# GSM_GPS.net
KiCad netlist of a schematic drawn in Altium Designer
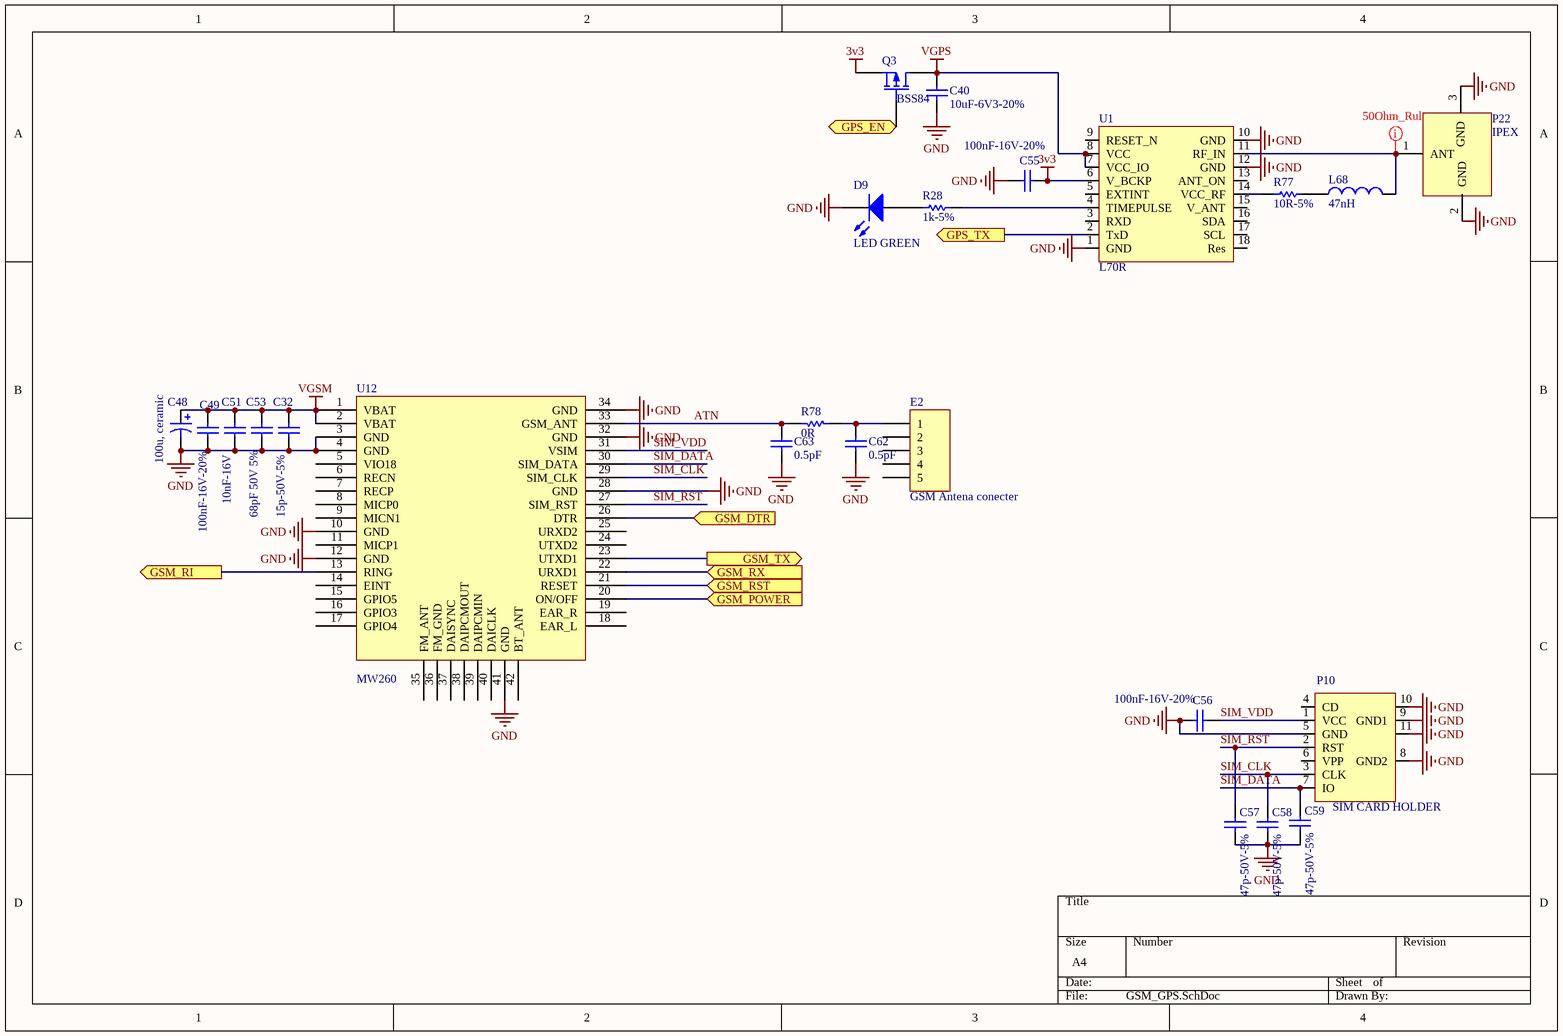
[diagram p0: GSM_GPS.SchDoc]

(export (version "E")
  (design (tool "Eeschema 10.0.6"))
  (components
    (comp (ref "C32")
      (value "15p-50V-5%")
      (footprint "C0402")
      (description "CAP CER 15PF 50V 5% NPO 0402")
      (fields
        (field (name "MANUFACTURER") "Yageo")
        (field (name "DIGI-KEY PART NUMBER") "311-1017-1-ND")
        (field (name "PUBLISHER") "Altium Limited")
      )
      (libsource (lib "Miscellaneous Devices") (part "Cap"))
    )
    (comp (ref "C40")
      (value "10uF-6V3-20%")
      (footprint "C0603")
      (description "CAP CER 10UF 6.3V 20% X5R 0603")
      (fields
        (field (name "MANUFACTURER") "Murata Electronics North America")
        (field (name "DIGI-KEY PART NUMBER") "490-3896-1-ND")
        (field (name "PUBLISHER") "Altium Limited")
      )
      (libsource (lib "Miscellaneous Devices") (part "Cap"))
    )
    (comp (ref "C48")
      (value "100u, ceramic")
      (footprint "C1812")
      (description "CAP CER 100UF 10V 20% X5R 1812")
      (fields
        (field (name "DIGI-KEY PART NUMBER") "445-7743-2-ND")
        (field (name "MANUFACTURER PART NUMBER") "C4532X5R1A107M")
        (field (name "PUBLISHER") "Altium Limited")
      )
      (libsource (lib "Miscellaneous Devices") (part "Cap Pol3"))
    )
    (comp (ref "C49")
      (value "100nF-16V-20%")
      (footprint "C0402")
      (description "CAP CER 0.1UF 16V Y5V 0402")
      (fields
        (field (name "MANUFACTURER") "Yageo")
        (field (name "DIGI-KEY PART NUMBER") "311-1047-1-ND")
        (field (name "PUBLISHER") "Altium Limited")
      )
      (libsource (lib "Miscellaneous Devices") (part "Cap"))
    )
    (comp (ref "C51")
      (value "10nF-16V")
      (footprint "C0402")
      (description "CAP CER 10000PF 16V 10% X7R 0402")
      (fields (field (name "DIGI-KEY PART NUMBER") "311-1042-2-ND") (field (name "MANUFACTURER") "Yageo"))
      (libsource (lib "Capacitor_0402") (part "10nF-16V-C0402-10%"))
    )
    (comp (ref "C53")
      (value "68pF 50V 5%")
      (footprint "C0402")
      (description "CAP CER 68PF 50V 5% NPO 0402")
      (fields (field (name "MANUFACTURER") "Yageo") (field (name "DIGI-KEY PART NUMBER") "311-1340-2-ND"))
      (libsource (lib "Miscellaneous Devices") (part "Cap"))
    )
    (comp (ref "C55")
      (value "100nF-16V-20%")
      (footprint "C0402")
      (description "CAP CER 0.1UF 16V Y5V 0402")
      (fields
        (field (name "MANUFACTURER") "Yageo")
        (field (name "DIGI-KEY PART NUMBER") "311-1047-1-ND")
        (field (name "PUBLISHER") "Altium Limited")
      )
      (libsource (lib "Miscellaneous Devices") (part "Cap"))
    )
    (comp (ref "C56")
      (value "100nF-16V-20%")
      (footprint "C0402")
      (description "CAP CER 0.1UF 16V Y5V 0402")
      (fields
        (field (name "MANUFACTURER") "Yageo")
        (field (name "DIGI-KEY PART NUMBER") "311-1047-1-ND")
        (field (name "PUBLISHER") "Altium Limited")
      )
      (libsource (lib "Miscellaneous Devices") (part "Cap"))
    )
    (comp (ref "C57")
      (value "47p-50V-5%")
      (footprint "C0402")
      (description "CAP CER 47PF 50V 5% NPO 0402")
      (fields
        (field (name "MANUFACTURER") "Yageo")
        (field (name "DIGI-KEY PART NUMBER") "311-1021-1-ND")
        (field (name "PUBLISHER") "Altium Limited")
      )
      (libsource (lib "Miscellaneous Devices") (part "Cap"))
    )
    (comp (ref "C58")
      (value "47p-50V-5%")
      (footprint "C0402")
      (description "CAP CER 47PF 50V 5% NPO 0402")
      (fields
        (field (name "MANUFACTURER") "Yageo")
        (field (name "DIGI-KEY PART NUMBER") "311-1021-1-ND")
        (field (name "PUBLISHER") "Altium Limited")
      )
      (libsource (lib "Miscellaneous Devices") (part "Cap"))
    )
    (comp (ref "C59")
      (value "47p-50V-5%")
      (footprint "C0402")
      (description "CAP CER 47PF 50V 5% NPO 0402")
      (fields
        (field (name "MANUFACTURER") "Yageo")
        (field (name "DIGI-KEY PART NUMBER") "311-1021-1-ND")
        (field (name "PUBLISHER") "Altium Limited")
      )
      (libsource (lib "Miscellaneous Devices") (part "Cap"))
    )
    (comp (ref "C62")
      (value "0.5pF")
      (footprint "C0402")
      (description "Non-Polarized Capacitor")
      (fields (field (name "DIGI-KEY PART NUMBER") "311-1094-1-ND") (field (name "MANUFACTURER") "Yageo"))
      (libsource (lib "Capacitor") (part "0.5pF-50V-C0805"))
    )
    (comp (ref "C63")
      (value "0.5pF")
      (footprint "C0402")
      (description "Non-Polarized Capacitor")
      (fields (field (name "DIGI-KEY PART NUMBER") "311-1094-1-ND") (field (name "MANUFACTURER") "Yageo"))
      (libsource (lib "Capacitor") (part "0.5pF-50V-C0805"))
    )
    (comp (ref "D9")
      (value "LED GREEN")
      (footprint "LED0603-G")
      (description "LED GREEN CLEAR THIN 0603 SMD")
      (fields
        (field (name "DIGI-KEY PART NUMBER") "160-1446-2-ND")
        (field (name "MANUFACTURER") "Lite-On Inc")
        (field (name "PUBLISHER") "Altium Limited")
      )
      (libsource (lib "Miscellaneous Devices") (part "LED2"))
    )
    (comp (ref "E2")
      (value "GSM Antena conecter")
      (footprint "A10343-GSM850/900/1800/1900/WCDMA")
      (description "Header, 5-Pin")
      (fields (field (name "PUBLISHER") "Altium Limited"))
      (libsource (lib "Miscellaneous Connectors") (part "Header 5"))
    )
    (comp (ref "L68")
      (value "47nH")
      (footprint "C0603")
      (description "Inductor")
      (fields (field (name "PUBLISHER") "Altium Limited"))
      (libsource (lib "Miscellaneous Devices") (part "Inductor"))
    )
    (comp (ref "P10")
      (value "SIM CARD HOLDER")
      (footprint "SIM MF01-412-063X")
      (description "SIM _CONNECTOR_410108105011-2LF")
      (fields (field (name "MANUFACTURER") "Tyrone"))
      (libsource (lib "Schlib1") (part "SIM CARD"))
    )
    (comp (ref "P22") (value "IPEX") (footprint "IPEX") (libsource (lib "Schlib1") (part "IPEX")))
    (comp (ref "Q3")
      (value "BSS84")
      (footprint "SOT23-3")
      (description "MOSFET P-CH 50V 130MA SOT23-3")
      (fields
        (field (name "DIGI-KEY PART NUMBER") "BSS84-FDITR-ND")
        (field (name "MANUFACTURER") "Diodes Inc")
        (field (name "PUBLISHER") "Altium Limited")
      )
      (libsource (lib "Miscellaneous Devices") (part "MOSFET-P"))
    )
    (comp (ref "R28")
      (value "1k-5%")
      (footprint "R0402")
      (description "RES 1.0K OHM 1/16W 5% 0402 SMD")
      (fields
        (field (name "DIGI-KEY PART NUMBER") "311-1.0KJRCT-ND")
        (field (name "MANUFACTURER") "Yageo")
        (field (name "PUBLISHER") "Altium Limited")
      )
      (libsource (lib "Miscellaneous Devices") (part "Res1"))
    )
    (comp (ref "R77")
      (value "10R-5%")
      (footprint "R0402")
      (description "RES 10 OHM 1/16W 5% 0402 SMD")
      (fields (field (name "DIGI-KEY PART NUMBER") "311-10JRTR-ND") (field (name "MANUFACTURER") "Yageo"))
      (libsource (lib "Resistor_0402") (part "10R-5%-R0402"))
    )
    (comp (ref "R78") (value "0R") (footprint "R0402") (libsource (lib "All_Resistor") (part "0R-0805")))
    (comp (ref "U1") (value "L70R") (footprint "MAX7") (libsource (lib "U-Blox") (part "MAX-7")))
    (comp (ref "U12")
      (value "MW260")
      (footprint "MW260-MODIFY")
      (description "THINK WILL GSM MODULE")
      (libsource (lib "Others") (part "GSM_MW260"))
    )
  )
  (nets
    (net (code "1") (name "/ATN") (class "Default")
      (node (ref "C63") (pin "2") (pinfunction "2_2") (pintype "passive"))
      (node (ref "R78") (pin "1") (pinfunction "1_1") (pintype "passive"))
      (node (ref "U12") (pin "33") (pinfunction "GSM_ANT_33") (pintype "passive"))
    )
    (net (code "2") (name "/GPS_EN") (class "Default")
      (node (ref "Q3") (pin "1") (pinfunction "G_1") (pintype "passive"))
    )
    (net (code "3") (name "/GPS_TX") (class "Default")
      (node (ref "U1") (pin "2") (pinfunction "TxD_2") (pintype "passive"))
    )
    (net (code "4") (name "/GSM_DTR") (class "Default")
      (node (ref "U12") (pin "26") (pinfunction "DTR_26") (pintype "passive"))
    )
    (net (code "5") (name "/GSM_POWER") (class "Default")
      (node (ref "U12") (pin "20") (pinfunction "ON/OFF_20") (pintype "passive"))
    )
    (net (code "6") (name "/GSM_RI") (class "Default")
      (node (ref "U12") (pin "13") (pinfunction "RING_13") (pintype "passive"))
    )
    (net (code "7") (name "/GSM_RST") (class "Default")
      (node (ref "U12") (pin "21") (pinfunction "RESET_21") (pintype "passive"))
    )
    (net (code "8") (name "/GSM_RX") (class "Default")
      (node (ref "U12") (pin "22") (pinfunction "URXD1_22") (pintype "passive"))
    )
    (net (code "9") (name "/GSM_TX") (class "Default")
      (node (ref "U12") (pin "23") (pinfunction "UTXD1_23") (pintype "passive"))
    )
    (net (code "10") (name "/SIM_CLK") (class "Default")
      (node (ref "C58") (pin "2") (pinfunction "2_2") (pintype "passive"))
      (node (ref "P10") (pin "3") (pinfunction "CLK_3") (pintype "passive"))
      (node (ref "U12") (pin "29") (pinfunction "SIM_CLK_29") (pintype "passive"))
    )
    (net (code "11") (name "/SIM_DATA") (class "Default")
      (node (ref "C59") (pin "2") (pinfunction "2_2") (pintype "passive"))
      (node (ref "P10") (pin "7") (pinfunction "IO_7") (pintype "passive"))
      (node (ref "U12") (pin "30") (pinfunction "SIM_DATA_30") (pintype "passive"))
    )
    (net (code "12") (name "/SIM_RST") (class "Default")
      (node (ref "C57") (pin "2") (pinfunction "2_2") (pintype "passive"))
      (node (ref "P10") (pin "2") (pinfunction "RST_2") (pintype "passive"))
      (node (ref "U12") (pin "27") (pinfunction "SIM_RST_27") (pintype "passive"))
    )
    (net (code "13") (name "/SIM_VDD") (class "Default")
      (node (ref "C56") (pin "1") (pinfunction "1_1") (pintype "passive"))
      (node (ref "P10") (pin "1") (pinfunction "VCC_1") (pintype "passive"))
      (node (ref "U12") (pin "31") (pinfunction "VSIM_31") (pintype "passive"))
    )
    (net (code "14") (name "3v3") (class "Default")
      (node (ref "C55") (pin "1") (pinfunction "1_1") (pintype "passive"))
      (node (ref "Q3") (pin "2") (pinfunction "S_2") (pintype "passive"))
      (node (ref "U1") (pin "6") (pinfunction "V_BCKP_6") (pintype "passive"))
    )
    (net (code "15") (name "GND") (class "Default")
      (node (ref "C32") (pin "2") (pinfunction "2_2") (pintype "passive"))
      (node (ref "C40") (pin "1") (pinfunction "1_1") (pintype "passive"))
      (node (ref "C48") (pin "2") (pinfunction "2_2") (pintype "passive"))
      (node (ref "C49") (pin "2") (pinfunction "2_2") (pintype "passive"))
      (node (ref "C51") (pin "1") (pinfunction "1_1") (pintype "passive"))
      (node (ref "C53") (pin "2") (pinfunction "2_2") (pintype "passive"))
      (node (ref "C55") (pin "2") (pinfunction "2_2") (pintype "passive"))
      (node (ref "C56") (pin "2") (pinfunction "2_2") (pintype "passive"))
      (node (ref "C57") (pin "1") (pinfunction "1_1") (pintype "passive"))
      (node (ref "C58") (pin "1") (pinfunction "1_1") (pintype "passive"))
      (node (ref "C59") (pin "1") (pinfunction "1_1") (pintype "passive"))
      (node (ref "C62") (pin "1") (pinfunction "1_1") (pintype "passive"))
      (node (ref "C63") (pin "1") (pinfunction "1_1") (pintype "passive"))
      (node (ref "D9") (pin "2") (pinfunction "K_2") (pintype "passive"))
      (node (ref "P10") (pin "10") (pinfunction "GND3_10") (pintype "passive"))
      (node (ref "P10") (pin "11") (pinfunction "GND4_11") (pintype "passive"))
      (node (ref "P10") (pin "5") (pinfunction "GND_5") (pintype "passive"))
      (node (ref "P10") (pin "8") (pinfunction "GND2_8") (pintype "passive"))
      (node (ref "P10") (pin "9") (pinfunction "GND1_9") (pintype "passive"))
      (node (ref "P22") (pin "2") (pinfunction "GND_2") (pintype "passive"))
      (node (ref "P22") (pin "3") (pinfunction "GND_3") (pintype "passive"))
      (node (ref "U1") (pin "1") (pinfunction "GND_1") (pintype "passive"))
      (node (ref "U1") (pin "10") (pinfunction "GND_10") (pintype "passive"))
      (node (ref "U1") (pin "12") (pinfunction "GND_12") (pintype "passive"))
      (node (ref "U12") (pin "10") (pinfunction "GND_10") (pintype "passive"))
      (node (ref "U12") (pin "12") (pinfunction "GND_12") (pintype "passive"))
      (node (ref "U12") (pin "28") (pinfunction "GND_28") (pintype "passive"))
      (node (ref "U12") (pin "3") (pinfunction "GND_3") (pintype "passive"))
      (node (ref "U12") (pin "32") (pinfunction "GND_32") (pintype "passive"))
      (node (ref "U12") (pin "34") (pinfunction "GND_34") (pintype "passive"))
      (node (ref "U12") (pin "4") (pinfunction "GND_4") (pintype "passive"))
      (node (ref "U12") (pin "41") (pinfunction "GND_41") (pintype "passive"))
    )
    (net (code "16") (name "Net-(C62-Pad2)") (class "Default")
      (node (ref "C62") (pin "2") (pinfunction "2_2") (pintype "passive"))
      (node (ref "E2") (pin "1") (pinfunction "1_1") (pintype "passive"))
      (node (ref "R78") (pin "2") (pinfunction "2_2") (pintype "passive"))
    )
    (net (code "17") (name "Net-(D9-A)") (class "Default")
      (node (ref "D9") (pin "1") (pinfunction "A_1") (pintype "passive"))
      (node (ref "R28") (pin "2") (pinfunction "2_2") (pintype "passive"))
    )
    (net (code "18") (name "Net-(L68-Pad1)") (class "Default")
      (node (ref "L68") (pin "1") (pinfunction "1_1") (pintype "passive"))
      (node (ref "R77") (pin "1") (pinfunction "1_1") (pintype "passive"))
    )
    (net (code "19") (name "Net-(P22-ANT)") (class "Default")
      (node (ref "L68") (pin "2") (pinfunction "2_2") (pintype "passive"))
      (node (ref "P22") (pin "1") (pinfunction "ANT_1") (pintype "passive"))
      (node (ref "U1") (pin "11") (pinfunction "RF_IN_11") (pintype "passive"))
    )
    (net (code "20") (name "Net-(U1-TIMEPULSE)") (class "Default")
      (node (ref "R28") (pin "1") (pinfunction "1_1") (pintype "passive"))
      (node (ref "U1") (pin "4") (pinfunction "TIMEPULSE_4") (pintype "passive"))
    )
    (net (code "21") (name "Net-(U1-VCC_RF)") (class "Default")
      (node (ref "R77") (pin "2") (pinfunction "2_2") (pintype "passive"))
      (node (ref "U1") (pin "14") (pinfunction "VCC_RF_14") (pintype "passive"))
    )
    (net (code "22") (name "VGPS") (class "Default")
      (node (ref "C40") (pin "2") (pinfunction "2_2") (pintype "passive"))
      (node (ref "Q3") (pin "3") (pinfunction "D_3") (pintype "passive"))
      (node (ref "U1") (pin "7") (pinfunction "VCC_IO_7") (pintype "passive"))
      (node (ref "U1") (pin "8") (pinfunction "VCC_8") (pintype "passive"))
    )
    (net (code "23") (name "VGSM") (class "Default")
      (node (ref "C32") (pin "1") (pinfunction "1_1") (pintype "passive"))
      (node (ref "C48") (pin "1") (pinfunction "1_1") (pintype "passive"))
      (node (ref "C49") (pin "1") (pinfunction "1_1") (pintype "passive"))
      (node (ref "C51") (pin "2") (pinfunction "2_2") (pintype "passive"))
      (node (ref "C53") (pin "1") (pinfunction "1_1") (pintype "passive"))
      (node (ref "U12") (pin "1") (pinfunction "VBAT_1") (pintype "passive"))
      (node (ref "U12") (pin "2") (pinfunction "VBAT_2") (pintype "passive"))
    )
    (net (code "24") (name "unconnected-(E2-Pad2)") (class "Default")
      (node (ref "E2") (pin "2") (pinfunction "2_2") (pintype "passive"))
    )
    (net (code "25") (name "unconnected-(E2-Pad3)") (class "Default")
      (node (ref "E2") (pin "3") (pinfunction "3_3") (pintype "passive"))
    )
    (net (code "26") (name "unconnected-(E2-Pad4)") (class "Default")
      (node (ref "E2") (pin "4") (pinfunction "4_4") (pintype "passive"))
    )
    (net (code "27") (name "unconnected-(E2-Pad5)") (class "Default")
      (node (ref "E2") (pin "5") (pinfunction "5_5") (pintype "passive"))
    )
    (net (code "28") (name "unconnected-(P10-CD-Pad4)") (class "Default")
      (node (ref "P10") (pin "4") (pinfunction "CD_4") (pintype "passive"))
    )
    (net (code "29") (name "unconnected-(P10-VPP-Pad6)") (class "Default")
      (node (ref "P10") (pin "6") (pinfunction "VPP_6") (pintype "passive"))
    )
    (net (code "30") (name "unconnected-(U1-ANT_ON-Pad13)") (class "Default")
      (node (ref "U1") (pin "13") (pinfunction "ANT_ON_13") (pintype "passive"))
    )
    (net (code "31") (name "unconnected-(U1-EXTINT-Pad5)") (class "Default")
      (node (ref "U1") (pin "5") (pinfunction "EXTINT_5") (pintype "passive"))
    )
    (net (code "32") (name "unconnected-(U1-RESET_N-Pad9)") (class "Default")
      (node (ref "U1") (pin "9") (pinfunction "RESET_N_9") (pintype "passive"))
    )
    (net (code "33") (name "unconnected-(U1-RXD-Pad3)") (class "Default")
      (node (ref "U1") (pin "3") (pinfunction "RXD_3") (pintype "passive"))
    )
    (net (code "34") (name "unconnected-(U1-Res-Pad18)") (class "Default")
      (node (ref "U1") (pin "18") (pinfunction "Res_18") (pintype "passive"))
    )
    (net (code "35") (name "unconnected-(U1-SCL-Pad17)") (class "Default")
      (node (ref "U1") (pin "17") (pinfunction "SCL_17") (pintype "passive"))
    )
    (net (code "36") (name "unconnected-(U1-SDA-Pad16)") (class "Default")
      (node (ref "U1") (pin "16") (pinfunction "SDA_16") (pintype "passive"))
    )
    (net (code "37") (name "unconnected-(U1-V_ANT-Pad15)") (class "Default")
      (node (ref "U1") (pin "15") (pinfunction "V_ANT_15") (pintype "passive"))
    )
    (net (code "38") (name "unconnected-(U12-BT_ANT-Pad42)") (class "Default")
      (node (ref "U12") (pin "42") (pinfunction "BT_ANT_42") (pintype "passive"))
    )
    (net (code "39") (name "unconnected-(U12-DAICLK-Pad40)") (class "Default")
      (node (ref "U12") (pin "40") (pinfunction "DAICLK_40") (pintype "passive"))
    )
    (net (code "40") (name "unconnected-(U12-DAIPCMIN-Pad39)") (class "Default")
      (node (ref "U12") (pin "39") (pinfunction "DAIPCMIN_39") (pintype "passive"))
    )
    (net (code "41") (name "unconnected-(U12-DAIPCMOUT-Pad38)") (class "Default")
      (node (ref "U12") (pin "38") (pinfunction "DAIPCMOUT_38") (pintype "passive"))
    )
    (net (code "42") (name "unconnected-(U12-DAISYNC-Pad37)") (class "Default")
      (node (ref "U12") (pin "37") (pinfunction "DAISYNC_37") (pintype "passive"))
    )
    (net (code "43") (name "unconnected-(U12-EAR_L-Pad18)") (class "Default")
      (node (ref "U12") (pin "18") (pinfunction "EAR_L_18") (pintype "passive"))
    )
    (net (code "44") (name "unconnected-(U12-EAR_R-Pad19)") (class "Default")
      (node (ref "U12") (pin "19") (pinfunction "EAR_R_19") (pintype "passive"))
    )
    (net (code "45") (name "unconnected-(U12-EINT-Pad14)") (class "Default")
      (node (ref "U12") (pin "14") (pinfunction "EINT_14") (pintype "passive"))
    )
    (net (code "46") (name "unconnected-(U12-FM_ANT-Pad35)") (class "Default")
      (node (ref "U12") (pin "35") (pinfunction "FM_ANT_35") (pintype "passive"))
    )
    (net (code "47") (name "unconnected-(U12-FM_GND-Pad36)") (class "Default")
      (node (ref "U12") (pin "36") (pinfunction "FM_GND_36") (pintype "passive"))
    )
    (net (code "48") (name "unconnected-(U12-GPIO3-Pad16)") (class "Default")
      (node (ref "U12") (pin "16") (pinfunction "GPIO3_16") (pintype "passive"))
    )
    (net (code "49") (name "unconnected-(U12-GPIO4-Pad17)") (class "Default")
      (node (ref "U12") (pin "17") (pinfunction "GPIO4_17") (pintype "passive"))
    )
    (net (code "50") (name "unconnected-(U12-GPIO5-Pad15)") (class "Default")
      (node (ref "U12") (pin "15") (pinfunction "GPIO5_15") (pintype "passive"))
    )
    (net (code "51") (name "unconnected-(U12-MICN1-Pad9)") (class "Default")
      (node (ref "U12") (pin "9") (pinfunction "MICN1_9") (pintype "passive"))
    )
    (net (code "52") (name "unconnected-(U12-MICP0-Pad8)") (class "Default")
      (node (ref "U12") (pin "8") (pinfunction "MICP0_8") (pintype "passive"))
    )
    (net (code "53") (name "unconnected-(U12-MICP1-Pad11)") (class "Default")
      (node (ref "U12") (pin "11") (pinfunction "MICP1_11") (pintype "passive"))
    )
    (net (code "54") (name "unconnected-(U12-RECN-Pad6)") (class "Default")
      (node (ref "U12") (pin "6") (pinfunction "RECN_6") (pintype "passive"))
    )
    (net (code "55") (name "unconnected-(U12-RECP-Pad7)") (class "Default")
      (node (ref "U12") (pin "7") (pinfunction "RECP_7") (pintype "passive"))
    )
    (net (code "56") (name "unconnected-(U12-URXD2-Pad25)") (class "Default")
      (node (ref "U12") (pin "25") (pinfunction "URXD2_25") (pintype "passive"))
    )
    (net (code "57") (name "unconnected-(U12-UTXD2-Pad24)") (class "Default")
      (node (ref "U12") (pin "24") (pinfunction "UTXD2_24") (pintype "passive"))
    )
    (net (code "58") (name "unconnected-(U12-VIO18-Pad5)") (class "Default")
      (node (ref "U12") (pin "5") (pinfunction "VIO18_5") (pintype "passive"))
    )
  )
)
